# J-Link_On_Board_with_RA4M2.net
KiCad netlist of a schematic drawn in Altium Designer
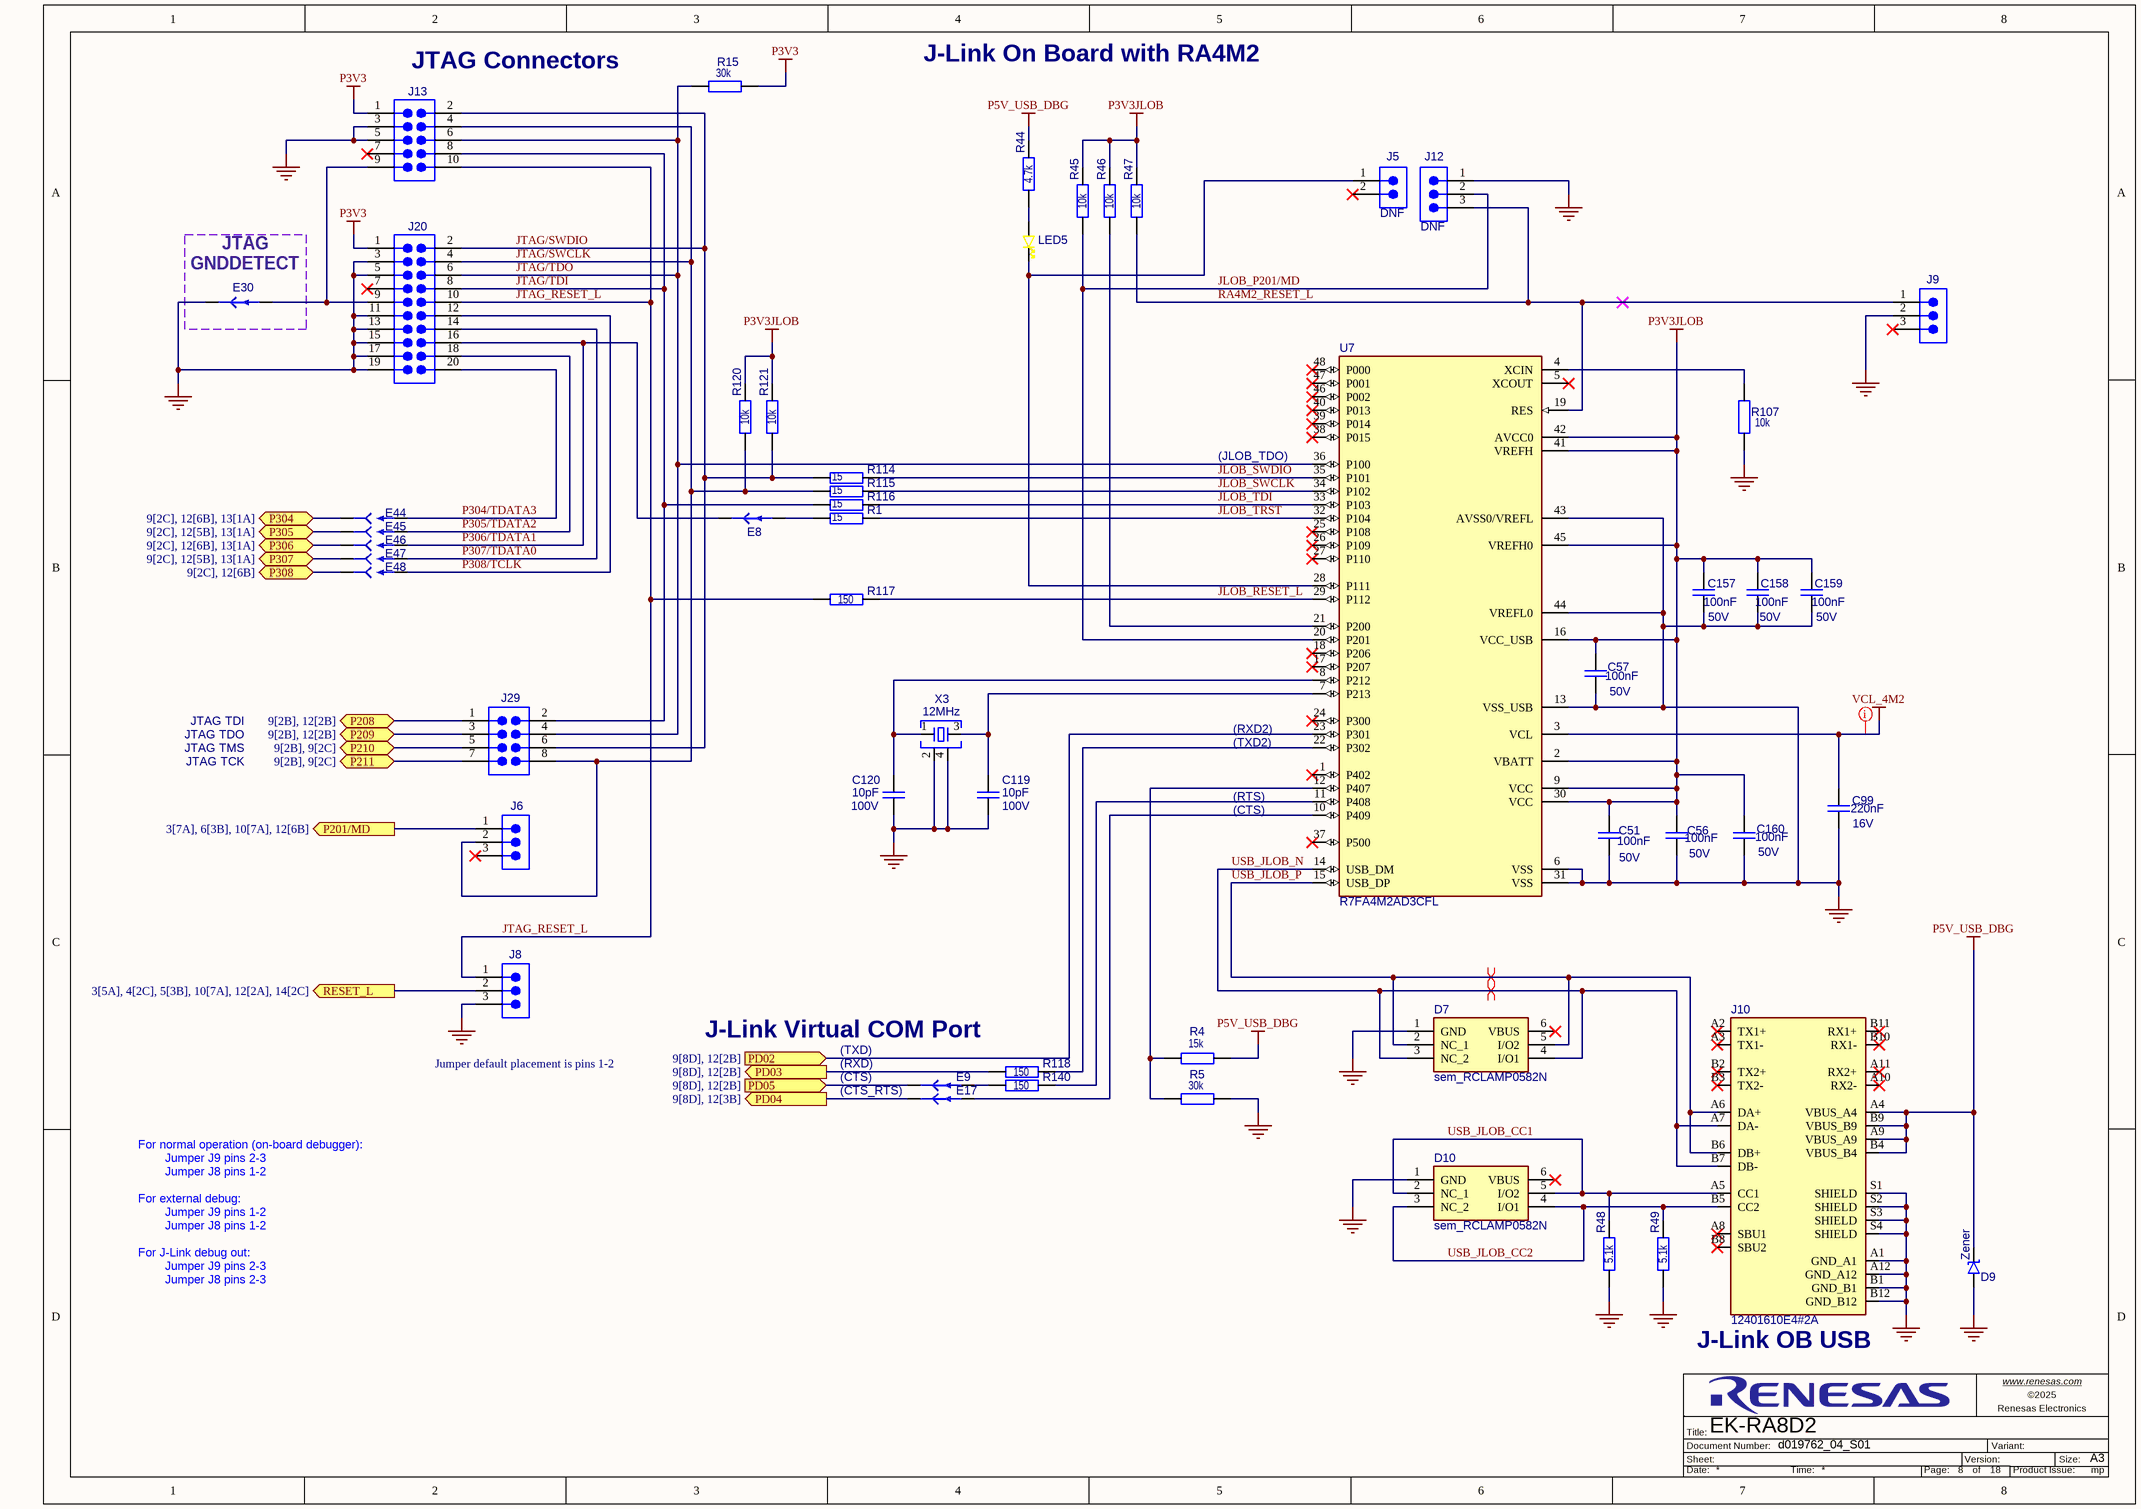
[diagram p0: J-Link On Board with RA4M2.SchDoc]

(export (version "E")
  (design (tool "Eeschema 10.0.6"))
  (components
    (comp (ref "C51")
      (value "100nF")
      (footprint "C_EIA0402_0p55")
      (description "Capacitor,EIA0402,100n,50V,X7R")
      (fields
        (field (name "TOLERANCE") "10%")
        (field (name "OPERATING VOLTAGE MAX") "50V")
        (field (name "Comment") "Capacitor")
      )
      (libsource (lib "ek-ra8d2_mp - Customer") (part "Capacitor"))
    )
    (comp (ref "C56")
      (value "100nF")
      (footprint "C_EIA0402_0p55")
      (description "Capacitor,EIA0402,100n,50V,X7R")
      (fields
        (field (name "TOLERANCE") "10%")
        (field (name "OPERATING VOLTAGE MAX") "50V")
        (field (name "Comment") "Capacitor")
      )
      (libsource (lib "ek-ra8d2_mp - Customer") (part "Capacitor"))
    )
    (comp (ref "C57")
      (value "100nF")
      (footprint "C_EIA0402_0p55")
      (description "Capacitor,EIA0402,100n,50V,X7R")
      (fields
        (field (name "TOLERANCE") "10%")
        (field (name "OPERATING VOLTAGE MAX") "50V")
        (field (name "Comment") "Capacitor")
      )
      (libsource (lib "ek-ra8d2_mp - Customer") (part "Capacitor"))
    )
    (comp (ref "C99")
      (value "220nF")
      (footprint "C_EIA0402_0p55")
      (description "Capacitor,EIA0402,220n,16V,X7R")
      (fields
        (field (name "TOLERANCE") "10%")
        (field (name "OPERATING VOLTAGE MAX") "16V")
        (field (name "Comment") "Capacitor")
      )
      (libsource (lib "ek-ra8d2_mp - Customer") (part "Capacitor"))
    )
    (comp (ref "C119")
      (value "10pF")
      (footprint "C_EIA0402_0p55")
      (description "Capacitor,EIA0402,10p,100V,C0G")
      (fields
        (field (name "TOLERANCE") "5%")
        (field (name "OPERATING VOLTAGE MAX") "100V")
        (field (name "Comment") "Capacitor")
      )
      (libsource (lib "ek-ra8d2_mp - Customer") (part "Capacitor"))
    )
    (comp (ref "C120")
      (value "10pF")
      (footprint "C_EIA0402_0p55")
      (description "Capacitor,EIA0402,10p,100V,C0G")
      (fields
        (field (name "TOLERANCE") "5%")
        (field (name "OPERATING VOLTAGE MAX") "100V")
        (field (name "Comment") "Capacitor")
      )
      (libsource (lib "ek-ra8d2_mp - Customer") (part "Capacitor"))
    )
    (comp (ref "C157")
      (value "100nF")
      (footprint "C_EIA0402_0p55")
      (description "Capacitor,EIA0402,100n,50V,X7R")
      (fields
        (field (name "TOLERANCE") "10%")
        (field (name "OPERATING VOLTAGE MAX") "50V")
        (field (name "Comment") "Capacitor")
      )
      (libsource (lib "ek-ra8d2_mp - Customer") (part "Capacitor"))
    )
    (comp (ref "C158")
      (value "100nF")
      (footprint "C_EIA0402_0p55")
      (description "Capacitor,EIA0402,100n,50V,X7R")
      (fields
        (field (name "TOLERANCE") "10%")
        (field (name "OPERATING VOLTAGE MAX") "50V")
        (field (name "Comment") "Capacitor")
      )
      (libsource (lib "ek-ra8d2_mp - Customer") (part "Capacitor"))
    )
    (comp (ref "C159")
      (value "100nF")
      (footprint "C_EIA0402_0p55")
      (description "Capacitor,EIA0402,100n,50V,X7R")
      (fields
        (field (name "TOLERANCE") "10%")
        (field (name "OPERATING VOLTAGE MAX") "50V")
        (field (name "Comment") "Capacitor")
      )
      (libsource (lib "ek-ra8d2_mp - Customer") (part "Capacitor"))
    )
    (comp (ref "C160")
      (value "100nF")
      (footprint "C_EIA0402_0p55")
      (description "Capacitor,EIA0402,100n,50V,X7R")
      (fields
        (field (name "TOLERANCE") "10%")
        (field (name "OPERATING VOLTAGE MAX") "50V")
        (field (name "Comment") "Capacitor")
      )
      (libsource (lib "ek-ra8d2_mp - Customer") (part "Capacitor"))
    )
    (comp (ref "D7")
      (value "sem_RCLAMP0582N")
      (footprint "sem_SLP-6_SLP1210N6")
      (description "Low Capacitance TVS Diode Array")
      (libsource (lib "ek-ra8d2_mp - Customer") (part "sem_RCLAMP0582N"))
    )
    (comp (ref "D9")
      (value "Zener")
      (footprint "sem_SGP-2_SGP1610N2")
      (description "ESD Suppressor Diode TVS Uni-Dir 22V 55Vc Automotive 2-Pin SGP T/R")
      (libsource (lib "ek-ra8d2_mp - Customer") (part "Zener"))
    )
    (comp (ref "D10")
      (value "sem_RCLAMP0582N")
      (footprint "sem_SLP-6_SLP1210N6")
      (description "Low Capacitance TVS Diode Array")
      (libsource (lib "ek-ra8d2_mp - Customer") (part "sem_RCLAMP0582N"))
    )
    (comp (ref "E8")
      (value "TRACE_CUT_0805")
      (footprint "trace_cut_0805")
      (description "Trace Cut, SMD, 0805 size")
      (libsource (lib "ek-ra8d2_mp - Customer") (part "trace_cut"))
    )
    (comp (ref "E9")
      (value "TRACE_CUT_0805")
      (footprint "trace_cut_0805")
      (description "Trace Cut, SMD, 0805 size")
      (libsource (lib "ek-ra8d2_mp - Customer") (part "trace_cut"))
    )
    (comp (ref "E17")
      (value "TRACE_CUT_0805")
      (footprint "trace_cut_0805")
      (description "Trace Cut, SMD, 0805 size")
      (libsource (lib "ek-ra8d2_mp - Customer") (part "trace_cut"))
    )
    (comp (ref "E30")
      (value "TRACE_CUT_0805")
      (footprint "trace_cut_0805")
      (description "Trace Cut, SMD, 0805 size")
      (libsource (lib "ek-ra8d2_mp - Customer") (part "trace_cut"))
    )
    (comp (ref "E44")
      (value "SOLDER_BRIDGE_0805")
      (footprint "solder_bridge_0805")
      (description "Solder Bridge, SMD, 0805 size")
      (libsource (lib "ek-ra8d2_mp - Customer") (part "solder_bridge"))
    )
    (comp (ref "E45")
      (value "SOLDER_BRIDGE_0805")
      (footprint "solder_bridge_0805")
      (description "Solder Bridge, SMD, 0805 size")
      (libsource (lib "ek-ra8d2_mp - Customer") (part "solder_bridge"))
    )
    (comp (ref "E46")
      (value "SOLDER_BRIDGE_0805")
      (footprint "solder_bridge_0805")
      (description "Solder Bridge, SMD, 0805 size")
      (libsource (lib "ek-ra8d2_mp - Customer") (part "solder_bridge"))
    )
    (comp (ref "E47")
      (value "SOLDER_BRIDGE_0805")
      (footprint "solder_bridge_0805")
      (description "Solder Bridge, SMD, 0805 size")
      (libsource (lib "ek-ra8d2_mp - Customer") (part "solder_bridge"))
    )
    (comp (ref "E48")
      (value "SOLDER_BRIDGE_0805")
      (footprint "solder_bridge_0805")
      (description "Solder Bridge, SMD, 0805 size")
      (libsource (lib "ek-ra8d2_mp - Customer") (part "solder_bridge"))
    )
    (comp (ref "J5")
      (value "NRPN021PAEN-RC")
      (footprint "sul_NRPN021PAEN-RC")
      (description "Header, 2way, 1row, vertical, 2.00mm, THT")
      (fields (field (name "DNF") "DNF"))
      (libsource (lib "ek-ra8d2_mp - Customer") (part "CON_002"))
    )
    (comp (ref "J6")
      (value "2842102-3")
      (footprint "tec_2842102-3")
      (description "Header, 3way, 1row, vertical, 2.00mm, SMD")
      (libsource (lib "ek-ra8d2_mp - Customer") (part "CON_003"))
    )
    (comp (ref "J8")
      (value "2842102-3")
      (footprint "tec_2842102-3")
      (description "Header, 3way, 1row, vertical, 2.00mm, SMD")
      (libsource (lib "ek-ra8d2_mp - Customer") (part "CON_003"))
    )
    (comp (ref "J9")
      (value "2842102-3")
      (footprint "tec_2842102-3")
      (description "Header, 3way, 1row, vertical, 2.00mm, SMD")
      (libsource (lib "ek-ra8d2_mp - Customer") (part "CON_003"))
    )
    (comp (ref "J10")
      (value "12401610E4#2A")
      (footprint "amp_12401610E42A")
      (description "Connector USB 3.2 Gen2 Type C Horizontal SMD")
      (libsource (lib "ek-ra8d2_mp - Customer") (part "USB3.2 Gen2_TypeC"))
    )
    (comp (ref "J12")
      (value "NRPN031PAEN-RC")
      (footprint "sul_NRPN031PAEN-RC")
      (description "Header, 3way, 1row, vertical, 2.00mm, THT")
      (fields (field (name "DNF") "DNF"))
      (libsource (lib "") (part "CON_003_1"))
    )
    (comp (ref "J13")
      (value "FTSH-105-01-F-DV-K-TR")
      (footprint "sam_FTSH-105-01-F-DV-K-TR")
      (description "Header,10way,2row,vertical,1.27mm,SMD")
      (libsource (lib "ek-ra8d2_mp - Customer") (part "CON_010"))
    )
    (comp (ref "J20")
      (value "FTSH-110-01-F-DV-K-TR")
      (footprint "sam_FTSH-110-01-L-DV-K-TR")
      (description "Header,20way,2row,vertical,1.27mm,SMD,gold flash on post")
      (libsource (lib "ek-ra8d2_mp - Customer") (part "CON_020"))
    )
    (comp (ref "J29")
      (value "NRPN042MAMS-RC")
      (footprint "sul_NRPN042MAMS-RC")
      (description "Header, 8way, 2row, vertical, 2.0mm, SMD")
      (libsource (lib "ek-ra8d2_mp - Customer") (part "CON_008"))
    )
    (comp (ref "LED5")
      (value "150060YS75000")
      (footprint "led_0603_y")
      (description "Standard LEDs - SMD Yellow, 590nm 90 to 120 mcd")
      (libsource (lib "ek-ra8d2_mp - Customer") (part "LED_yellow"))
    )
    (comp (ref "R1")
      (value "15")
      (footprint "R_EIA0402")
      (description "Resistor,EIA0402,15,0.0625W")
      (fields (field (name "TOLERANCE") "1%") (field (name "POWER") "62.5mW"))
      (libsource (lib "ek-ra8d2_mp - Customer") (part "Resistor"))
    )
    (comp (ref "R4")
      (value "15k")
      (footprint "R_EIA0402")
      (description "Resistor,EIA0402,15k,0.0625W")
      (fields (field (name "TOLERANCE") "1%") (field (name "POWER") "62.5mW"))
      (libsource (lib "") (part "Resistor_1"))
    )
    (comp (ref "R5")
      (value "30k")
      (footprint "R_EIA0402")
      (description "Resistor,EIA0402,30k,0.0625W")
      (fields (field (name "TOLERANCE") "1%") (field (name "POWER") "62.5mW"))
      (libsource (lib "ek-ra8d2_mp - Customer") (part "Resistor"))
    )
    (comp (ref "R15")
      (value "30k")
      (footprint "R_EIA0402")
      (description "Resistor,EIA0402,30k,0.0625W")
      (fields (field (name "TOLERANCE") "1%") (field (name "POWER") "62.5mW"))
      (libsource (lib "ek-ra8d2_mp - Customer") (part "Resistor"))
    )
    (comp (ref "R44")
      (value "4.7k")
      (footprint "R_EIA0402")
      (description "Resistor,EIA0402,4.7k,0.0625W")
      (fields (field (name "POWER") "62.5mW") (field (name "TOLERANCE") "1%"))
      (libsource (lib "") (part "Resistor_2"))
    )
    (comp (ref "R45")
      (value "10k")
      (footprint "R_EIA0402")
      (description "Resistor,EIA0402,10k,0.0625W")
      (fields (field (name "POWER") "62.5mW") (field (name "TOLERANCE") "1%"))
      (libsource (lib "") (part "Resistor_2"))
    )
    (comp (ref "R46")
      (value "10k")
      (footprint "R_EIA0402")
      (description "Resistor,EIA0402,10k,0.0625W")
      (fields (field (name "POWER") "62.5mW") (field (name "TOLERANCE") "1%"))
      (libsource (lib "") (part "Resistor_2"))
    )
    (comp (ref "R47")
      (value "10k")
      (footprint "R_EIA0402")
      (description "Resistor,EIA0402,10k,0.0625W")
      (fields (field (name "POWER") "62.5mW") (field (name "TOLERANCE") "1%"))
      (libsource (lib "") (part "Resistor_2"))
    )
    (comp (ref "R48")
      (value "5.1k")
      (footprint "R_EIA0402")
      (description "Resistor,EIA0402,5.1k,0.0625W")
      (fields (field (name "POWER") "62.5mW") (field (name "TOLERANCE") "1%"))
      (libsource (lib "") (part "Resistor_2"))
    )
    (comp (ref "R49")
      (value "5.1k")
      (footprint "R_EIA0402")
      (description "Resistor,EIA0402,5.1k,0.0625W")
      (fields (field (name "POWER") "62.5mW") (field (name "TOLERANCE") "1%"))
      (libsource (lib "") (part "Resistor_2"))
    )
    (comp (ref "R107")
      (value "10k")
      (footprint "R_EIA0402")
      (description "Resistor,EIA0402,10k,0.0625W")
      (fields (field (name "POWER") "62.5mW") (field (name "TOLERANCE") "1%"))
      (libsource (lib "") (part "Resistor_2"))
    )
    (comp (ref "R114")
      (value "15")
      (footprint "R_EIA0402")
      (description "Resistor,EIA0402,15,0.0625W")
      (fields (field (name "TOLERANCE") "1%") (field (name "POWER") "62.5mW"))
      (libsource (lib "ek-ra8d2_mp - Customer") (part "Resistor"))
    )
    (comp (ref "R115")
      (value "15")
      (footprint "R_EIA0402")
      (description "Resistor,EIA0402,15,0.0625W")
      (fields (field (name "TOLERANCE") "1%") (field (name "POWER") "62.5mW"))
      (libsource (lib "ek-ra8d2_mp - Customer") (part "Resistor"))
    )
    (comp (ref "R116")
      (value "15")
      (footprint "R_EIA0402")
      (description "Resistor,EIA0402,15,0.0625W")
      (fields (field (name "TOLERANCE") "1%") (field (name "POWER") "62.5mW"))
      (libsource (lib "ek-ra8d2_mp - Customer") (part "Resistor"))
    )
    (comp (ref "R117")
      (value "150")
      (footprint "R_EIA0402")
      (description "Resistor,EIA0402,150,0.0625W")
      (fields (field (name "POWER") "62.5mW") (field (name "TOLERANCE") "1%"))
      (libsource (lib "ek-ra8d2_mp - Customer") (part "Resistor"))
    )
    (comp (ref "R118")
      (value "150")
      (footprint "R_EIA0402")
      (description "Resistor,EIA0402,150,0.0625W")
      (fields (field (name "POWER") "62.5mW") (field (name "TOLERANCE") "1%"))
      (libsource (lib "ek-ra8d2_mp - Customer") (part "Resistor"))
    )
    (comp (ref "R120")
      (value "10k")
      (footprint "R_EIA0402")
      (description "Resistor,EIA0402,10k,0.0625W")
      (fields (field (name "POWER") "62.5mW") (field (name "TOLERANCE") "1%"))
      (libsource (lib "") (part "Resistor_2"))
    )
    (comp (ref "R121")
      (value "10k")
      (footprint "R_EIA0402")
      (description "Resistor,EIA0402,10k,0.0625W")
      (fields (field (name "POWER") "62.5mW") (field (name "TOLERANCE") "1%"))
      (libsource (lib "") (part "Resistor_2"))
    )
    (comp (ref "R140")
      (value "150")
      (footprint "R_EIA0402")
      (description "Resistor,EIA0402,150,0.0625W")
      (fields (field (name "POWER") "62.5mW") (field (name "TOLERANCE") "1%"))
      (libsource (lib "ek-ra8d2_mp - Customer") (part "Resistor"))
    )
    (comp (ref "U7")
      (value "R7FA4M2AD3CFL")
      (footprint "ren_LQFP-48_PLQP0048KB-B")
      (libsource (lib "ek-ra8d2_mp - Customer") (part "ren_R7FA4M2AD3CFL"))
    )
    (comp (ref "X3")
      (value "12MHz")
      (footprint "ecs_ECX-2236B")
      (description "Crystal, 12.000MHz, 10 pF, 2.5x2")
      (fields (field (name "TOLERANCE") "10ppm") (field (name "Comment") "ECS-120-10-36B-CWY-TR"))
      (libsource (lib "ek-ra8d2_mp - Customer") (part "Crystal_4pin"))
    )
  )
  (nets
    (net (code "1") (name "/JLOB_P201{slash}MD") (class "Default")
      (node (ref "J12") (pin "2") (pinfunction "2_2") (pintype "passive"))
      (node (ref "R45") (pin "1") (pinfunction "1_1") (pintype "passive"))
      (node (ref "U7") (pin "20") (pinfunction "P201_20") (pintype "bidirectional"))
    )
    (net (code "2") (name "/JLOB_RESET_L") (class "Default")
      (node (ref "R117") (pin "2") (pinfunction "2_2") (pintype "passive"))
      (node (ref "U7") (pin "29") (pinfunction "P112_29") (pintype "bidirectional"))
    )
    (net (code "3") (name "/JLOB_SWCLK") (class "Default")
      (node (ref "R115") (pin "2") (pinfunction "2_2") (pintype "passive"))
      (node (ref "U7") (pin "34") (pinfunction "P102_34") (pintype "bidirectional"))
    )
    (net (code "4") (name "/JLOB_SWDIO") (class "Default")
      (node (ref "R114") (pin "2") (pinfunction "2_2") (pintype "passive"))
      (node (ref "U7") (pin "35") (pinfunction "P101_35") (pintype "bidirectional"))
    )
    (net (code "5") (name "/JLOB_TDI") (class "Default")
      (node (ref "R116") (pin "2") (pinfunction "2_2") (pintype "passive"))
      (node (ref "U7") (pin "33") (pinfunction "P103_33") (pintype "bidirectional"))
    )
    (net (code "6") (name "/JLOB_TRST") (class "Default")
      (node (ref "R1") (pin "2") (pinfunction "2_2") (pintype "passive"))
      (node (ref "U7") (pin "32") (pinfunction "P104_32") (pintype "bidirectional"))
    )
    (net (code "7") (name "/JTAG_RESET_L") (class "Default")
      (node (ref "J13") (pin "10") (pinfunction "10_10") (pintype "passive"))
      (node (ref "J20") (pin "10") (pinfunction "10_10") (pintype "passive"))
      (node (ref "J8") (pin "1") (pinfunction "1_1") (pintype "passive"))
      (node (ref "R117") (pin "1") (pinfunction "1_1") (pintype "passive"))
    )
    (net (code "8") (name "/JTAG{slash}SWCLK") (class "Default")
      (node (ref "J13") (pin "4") (pinfunction "4_4") (pintype "passive"))
      (node (ref "J20") (pin "4") (pinfunction "4_4") (pintype "passive"))
      (node (ref "J29") (pin "8") (pinfunction "8_8") (pintype "passive"))
      (node (ref "J6") (pin "2") (pinfunction "2_2") (pintype "passive"))
      (node (ref "R115") (pin "1") (pinfunction "1_1") (pintype "passive"))
      (node (ref "R120") (pin "1") (pinfunction "1_1") (pintype "passive"))
    )
    (net (code "9") (name "/JTAG{slash}SWDIO") (class "Default")
      (node (ref "J13") (pin "2") (pinfunction "2_2") (pintype "passive"))
      (node (ref "J20") (pin "2") (pinfunction "2_2") (pintype "passive"))
      (node (ref "J29") (pin "6") (pinfunction "6_6") (pintype "passive"))
      (node (ref "R114") (pin "1") (pinfunction "1_1") (pintype "passive"))
      (node (ref "R121") (pin "1") (pinfunction "1_1") (pintype "passive"))
    )
    (net (code "10") (name "/JTAG{slash}TDI") (class "Default")
      (node (ref "J13") (pin "8") (pinfunction "8_8") (pintype "passive"))
      (node (ref "J20") (pin "8") (pinfunction "8_8") (pintype "passive"))
      (node (ref "J29") (pin "2") (pinfunction "2_2") (pintype "passive"))
      (node (ref "R116") (pin "1") (pinfunction "1_1") (pintype "passive"))
    )
    (net (code "11") (name "/JTAG{slash}TDO") (class "Default")
      (node (ref "J13") (pin "6") (pinfunction "6_6") (pintype "passive"))
      (node (ref "J20") (pin "6") (pinfunction "6_6") (pintype "passive"))
      (node (ref "J29") (pin "4") (pinfunction "4_4") (pintype "passive"))
      (node (ref "R15") (pin "1") (pinfunction "1_1") (pintype "passive"))
      (node (ref "U7") (pin "36") (pinfunction "P100_36") (pintype "bidirectional"))
    )
    (net (code "12") (name "/P201{slash}MD") (class "Default")
      (node (ref "J6") (pin "1") (pinfunction "1_1") (pintype "passive"))
    )
    (net (code "13") (name "/P208") (class "Default")
      (node (ref "J29") (pin "1") (pinfunction "1_1") (pintype "passive"))
    )
    (net (code "14") (name "/P209") (class "Default")
      (node (ref "J29") (pin "3") (pinfunction "3_3") (pintype "passive"))
    )
    (net (code "15") (name "/P210") (class "Default")
      (node (ref "J29") (pin "5") (pinfunction "5_5") (pintype "passive"))
    )
    (net (code "16") (name "/P211") (class "Default")
      (node (ref "J29") (pin "7") (pinfunction "7_7") (pintype "passive"))
    )
    (net (code "17") (name "/P304") (class "Default")
      (node (ref "E44") (pin "1") (pinfunction "1_1") (pintype "passive"))
    )
    (net (code "18") (name "/P304{slash}TDATA3") (class "Default")
      (node (ref "E44") (pin "2") (pinfunction "2_2") (pintype "passive"))
      (node (ref "J20") (pin "20") (pinfunction "20_20") (pintype "passive"))
    )
    (net (code "19") (name "/P305") (class "Default")
      (node (ref "E45") (pin "1") (pinfunction "1_1") (pintype "passive"))
    )
    (net (code "20") (name "/P305{slash}TDATA2") (class "Default")
      (node (ref "E45") (pin "2") (pinfunction "2_2") (pintype "passive"))
      (node (ref "J20") (pin "18") (pinfunction "18_18") (pintype "passive"))
    )
    (net (code "21") (name "/P306") (class "Default")
      (node (ref "E46") (pin "1") (pinfunction "1_1") (pintype "passive"))
    )
    (net (code "22") (name "/P306{slash}TDATA1") (class "Default")
      (node (ref "E46") (pin "2") (pinfunction "2_2") (pintype "passive"))
      (node (ref "E8") (pin "1") (pinfunction "1_1") (pintype "passive"))
      (node (ref "J20") (pin "16") (pinfunction "16_16") (pintype "passive"))
    )
    (net (code "23") (name "/P307") (class "Default")
      (node (ref "E47") (pin "1") (pinfunction "1_1") (pintype "passive"))
    )
    (net (code "24") (name "/P307{slash}TDATA0") (class "Default")
      (node (ref "E47") (pin "2") (pinfunction "2_2") (pintype "passive"))
      (node (ref "J20") (pin "14") (pinfunction "14_14") (pintype "passive"))
    )
    (net (code "25") (name "/P308") (class "Default")
      (node (ref "E48") (pin "1") (pinfunction "1_1") (pintype "passive"))
    )
    (net (code "26") (name "/P308{slash}TCLK") (class "Default")
      (node (ref "E48") (pin "2") (pinfunction "2_2") (pintype "passive"))
      (node (ref "J20") (pin "12") (pinfunction "12_12") (pintype "passive"))
    )
    (net (code "27") (name "/PD02") (class "Default")
      (node (ref "U7") (pin "23") (pinfunction "P301_23") (pintype "bidirectional"))
    )
    (net (code "28") (name "/PD03") (class "Default")
      (node (ref "R118") (pin "1") (pinfunction "1_1") (pintype "passive"))
    )
    (net (code "29") (name "/PD04") (class "Default")
      (node (ref "E17") (pin "1") (pinfunction "1_1") (pintype "passive"))
    )
    (net (code "30") (name "/PD05") (class "Default")
      (node (ref "E9") (pin "1") (pinfunction "1_1") (pintype "passive"))
    )
    (net (code "31") (name "/RA4M2_RESET_L") (class "Default")
      (node (ref "J12") (pin "3") (pinfunction "3_3") (pintype "passive"))
      (node (ref "J9") (pin "1") (pinfunction "1_1") (pintype "passive"))
      (node (ref "R47") (pin "1") (pinfunction "1_1") (pintype "passive"))
      (node (ref "U7") (pin "19") (pinfunction "RES_19") (pintype "input"))
    )
    (net (code "32") (name "/RESET_L") (class "Default")
      (node (ref "J8") (pin "2") (pinfunction "2_2") (pintype "passive"))
    )
    (net (code "33") (name "/USB_JLOB_CC1") (class "Default")
      (node (ref "D10") (pin "2") (pinfunction "NC_1_2") (pintype "passive"))
      (node (ref "D10") (pin "5") (pinfunction "I/O2_5") (pintype "passive"))
      (node (ref "J10") (pin "A5") (pinfunction "CC1_A5") (pintype "passive"))
      (node (ref "R48") (pin "2") (pinfunction "2_2") (pintype "passive"))
    )
    (net (code "34") (name "/USB_JLOB_CC2") (class "Default")
      (node (ref "D10") (pin "3") (pinfunction "NC_2_3") (pintype "passive"))
      (node (ref "D10") (pin "4") (pinfunction "I/O1_4") (pintype "passive"))
      (node (ref "J10") (pin "B5") (pinfunction "CC2_B5") (pintype "passive"))
      (node (ref "R49") (pin "2") (pinfunction "2_2") (pintype "passive"))
    )
    (net (code "35") (name "/USB_JLOB_N") (class "Default")
      (node (ref "D7") (pin "3") (pinfunction "NC_2_3") (pintype "passive"))
      (node (ref "D7") (pin "4") (pinfunction "I/O1_4") (pintype "passive"))
      (node (ref "J10") (pin "A7") (pinfunction "DA-_A7") (pintype "passive"))
      (node (ref "J10") (pin "B7") (pinfunction "DB-_B7") (pintype "passive"))
      (node (ref "U7") (pin "14") (pinfunction "USB_DM_14") (pintype "bidirectional"))
    )
    (net (code "36") (name "/USB_JLOB_P") (class "Default")
      (node (ref "D7") (pin "2") (pinfunction "NC_1_2") (pintype "passive"))
      (node (ref "D7") (pin "5") (pinfunction "I/O2_5") (pintype "passive"))
      (node (ref "J10") (pin "A6") (pinfunction "DA+_A6") (pintype "passive"))
      (node (ref "J10") (pin "B6") (pinfunction "DB+_B6") (pintype "passive"))
      (node (ref "U7") (pin "15") (pinfunction "USB_DP_15") (pintype "bidirectional"))
    )
    (net (code "37") (name "GND") (class "Default")
      (node (ref "C119") (pin "2") (pinfunction "2_2") (pintype "passive"))
      (node (ref "C120") (pin "2") (pinfunction "2_2") (pintype "passive"))
      (node (ref "C157") (pin "1") (pinfunction "1_1") (pintype "passive"))
      (node (ref "C158") (pin "1") (pinfunction "1_1") (pintype "passive"))
      (node (ref "C159") (pin "1") (pinfunction "1_1") (pintype "passive"))
      (node (ref "C160") (pin "1") (pinfunction "1_1") (pintype "passive"))
      (node (ref "C51") (pin "1") (pinfunction "1_1") (pintype "passive"))
      (node (ref "C56") (pin "1") (pinfunction "1_1") (pintype "passive"))
      (node (ref "C57") (pin "1") (pinfunction "1_1") (pintype "passive"))
      (node (ref "C99") (pin "1") (pinfunction "1_1") (pintype "passive"))
      (node (ref "D10") (pin "1") (pinfunction "GND_1") (pintype "passive"))
      (node (ref "D7") (pin "1") (pinfunction "GND_1") (pintype "passive"))
      (node (ref "D9") (pin "2") (pinfunction "A_2") (pintype "passive"))
      (node (ref "E30") (pin "1") (pinfunction "1_1") (pintype "passive"))
      (node (ref "J10") (pin "A1") (pinfunction "GND_A1_A1") (pintype "passive"))
      (node (ref "J10") (pin "A12") (pinfunction "GND_A12_A12") (pintype "passive"))
      (node (ref "J10") (pin "B1") (pinfunction "GND_B1_B1") (pintype "passive"))
      (node (ref "J10") (pin "B12") (pinfunction "GND_B12_B12") (pintype "passive"))
      (node (ref "J10") (pin "S1") (pinfunction "SHIELD_S1") (pintype "passive"))
      (node (ref "J10") (pin "S2") (pinfunction "SHIELD_S2") (pintype "passive"))
      (node (ref "J10") (pin "S3") (pinfunction "SHIELD_S3") (pintype "passive"))
      (node (ref "J10") (pin "S4") (pinfunction "SHIELD_S4") (pintype "passive"))
      (node (ref "J12") (pin "1") (pinfunction "1_1") (pintype "passive"))
      (node (ref "J13") (pin "3") (pinfunction "3_3") (pintype "passive"))
      (node (ref "J13") (pin "5") (pinfunction "5_5") (pintype "passive"))
      (node (ref "J20") (pin "11") (pinfunction "11_11") (pintype "passive"))
      (node (ref "J20") (pin "13") (pinfunction "13_13") (pintype "passive"))
      (node (ref "J20") (pin "15") (pinfunction "15_15") (pintype "passive"))
      (node (ref "J20") (pin "17") (pinfunction "17_17") (pintype "passive"))
      (node (ref "J20") (pin "19") (pinfunction "19_19") (pintype "passive"))
      (node (ref "J20") (pin "3") (pinfunction "3_3") (pintype "passive"))
      (node (ref "J20") (pin "5") (pinfunction "5_5") (pintype "passive"))
      (node (ref "J8") (pin "3") (pinfunction "3_3") (pintype "passive"))
      (node (ref "J9") (pin "2") (pinfunction "2_2") (pintype "passive"))
      (node (ref "R107") (pin "1") (pinfunction "1_1") (pintype "passive"))
      (node (ref "R48") (pin "1") (pinfunction "1_1") (pintype "passive"))
      (node (ref "R49") (pin "1") (pinfunction "1_1") (pintype "passive"))
      (node (ref "R5") (pin "2") (pinfunction "2_2") (pintype "passive"))
      (node (ref "U7") (pin "13") (pinfunction "VSS_USB_13") (pintype "power_in"))
      (node (ref "U7") (pin "31") (pinfunction "VSS_31") (pintype "power_in"))
      (node (ref "U7") (pin "43") (pinfunction "AVSS0/VREFL_43") (pintype "power_in"))
      (node (ref "U7") (pin "44") (pinfunction "VREFL0_44") (pintype "power_in"))
      (node (ref "U7") (pin "6") (pinfunction "VSS_6") (pintype "power_in"))
      (node (ref "X3") (pin "2") (pinfunction "2_2") (pintype "passive"))
      (node (ref "X3") (pin "4") (pinfunction "4_4") (pintype "passive"))
    )
    (net (code "38") (name "Net-(E8-Pad2)") (class "Default")
      (node (ref "E8") (pin "2") (pinfunction "2_2") (pintype "passive"))
      (node (ref "R1") (pin "1") (pinfunction "1_1") (pintype "passive"))
    )
    (net (code "39") (name "Net-(E9-Pad2)") (class "Default")
      (node (ref "E9") (pin "2") (pinfunction "2_2") (pintype "passive"))
      (node (ref "R140") (pin "1") (pinfunction "1_1") (pintype "passive"))
    )
    (net (code "40") (name "Net-(E30-Pad2)") (class "Default")
      (node (ref "E30") (pin "2") (pinfunction "2_2") (pintype "passive"))
      (node (ref "J13") (pin "9") (pinfunction "9_9") (pintype "passive"))
      (node (ref "J20") (pin "9") (pinfunction "9_9") (pintype "passive"))
    )
    (net (code "41") (name "Net-(LED5-A)") (class "Default")
      (node (ref "LED5") (pin "2") (pinfunction "A_2") (pintype "passive"))
      (node (ref "R44") (pin "1") (pinfunction "1_1") (pintype "passive"))
    )
    (net (code "42") (name "Net-(LED5-K)") (class "Default")
      (node (ref "J5") (pin "1") (pinfunction "1_1") (pintype "passive"))
      (node (ref "LED5") (pin "1") (pinfunction "K_1") (pintype "passive"))
      (node (ref "U7") (pin "28") (pinfunction "P111_28") (pintype "bidirectional"))
    )
    (net (code "43") (name "Net-(U7-P200)") (class "Default")
      (node (ref "R46") (pin "1") (pinfunction "1_1") (pintype "passive"))
      (node (ref "U7") (pin "21") (pinfunction "P200_21") (pintype "bidirectional"))
    )
    (net (code "44") (name "Net-(U7-P212)") (class "Default")
      (node (ref "C120") (pin "1") (pinfunction "1_1") (pintype "passive"))
      (node (ref "U7") (pin "8") (pinfunction "P212_8") (pintype "bidirectional"))
      (node (ref "X3") (pin "1") (pinfunction "1_1") (pintype "passive"))
    )
    (net (code "45") (name "Net-(U7-P213)") (class "Default")
      (node (ref "C119") (pin "1") (pinfunction "1_1") (pintype "passive"))
      (node (ref "U7") (pin "7") (pinfunction "P213_7") (pintype "bidirectional"))
      (node (ref "X3") (pin "3") (pinfunction "3_3") (pintype "passive"))
    )
    (net (code "46") (name "Net-(U7-P302)") (class "Default")
      (node (ref "R118") (pin "2") (pinfunction "2_2") (pintype "passive"))
      (node (ref "U7") (pin "22") (pinfunction "P302_22") (pintype "bidirectional"))
    )
    (net (code "47") (name "Net-(U7-P407)") (class "Default")
      (node (ref "R4") (pin "2") (pinfunction "2_2") (pintype "passive"))
      (node (ref "R5") (pin "1") (pinfunction "1_1") (pintype "passive"))
      (node (ref "U7") (pin "12") (pinfunction "P407_12") (pintype "bidirectional"))
    )
    (net (code "48") (name "Net-(U7-P408)") (class "Default")
      (node (ref "R140") (pin "2") (pinfunction "2_2") (pintype "passive"))
      (node (ref "U7") (pin "11") (pinfunction "P408_11") (pintype "bidirectional"))
    )
    (net (code "49") (name "Net-(U7-P409)") (class "Default")
      (node (ref "E17") (pin "2") (pinfunction "2_2") (pintype "passive"))
      (node (ref "U7") (pin "10") (pinfunction "P409_10") (pintype "bidirectional"))
    )
    (net (code "50") (name "Net-(U7-XCIN)") (class "Default")
      (node (ref "R107") (pin "2") (pinfunction "2_2") (pintype "passive"))
      (node (ref "U7") (pin "4") (pinfunction "XCIN_4") (pintype "passive"))
    )
    (net (code "51") (name "P3V3") (class "Default")
      (node (ref "J13") (pin "1") (pinfunction "1_1") (pintype "passive"))
      (node (ref "J20") (pin "1") (pinfunction "1_1") (pintype "passive"))
      (node (ref "R15") (pin "2") (pinfunction "2_2") (pintype "passive"))
    )
    (net (code "52") (name "P3V3JLOB") (class "Default")
      (node (ref "C157") (pin "2") (pinfunction "2_2") (pintype "passive"))
      (node (ref "C158") (pin "2") (pinfunction "2_2") (pintype "passive"))
      (node (ref "C159") (pin "2") (pinfunction "2_2") (pintype "passive"))
      (node (ref "C160") (pin "2") (pinfunction "2_2") (pintype "passive"))
      (node (ref "C51") (pin "2") (pinfunction "2_2") (pintype "passive"))
      (node (ref "C56") (pin "2") (pinfunction "2_2") (pintype "passive"))
      (node (ref "C57") (pin "2") (pinfunction "2_2") (pintype "passive"))
      (node (ref "R120") (pin "2") (pinfunction "2_2") (pintype "passive"))
      (node (ref "R121") (pin "2") (pinfunction "2_2") (pintype "passive"))
      (node (ref "R45") (pin "2") (pinfunction "2_2") (pintype "passive"))
      (node (ref "R46") (pin "2") (pinfunction "2_2") (pintype "passive"))
      (node (ref "R47") (pin "2") (pinfunction "2_2") (pintype "passive"))
      (node (ref "U7") (pin "16") (pinfunction "VCC_USB_16") (pintype "power_in"))
      (node (ref "U7") (pin "2") (pinfunction "VBATT_2") (pintype "power_in"))
      (node (ref "U7") (pin "30") (pinfunction "VCC_30") (pintype "power_in"))
      (node (ref "U7") (pin "41") (pinfunction "VREFH_41") (pintype "power_in"))
      (node (ref "U7") (pin "42") (pinfunction "AVCC0_42") (pintype "power_in"))
      (node (ref "U7") (pin "45") (pinfunction "VREFH0_45") (pintype "power_in"))
      (node (ref "U7") (pin "9") (pinfunction "VCC_9") (pintype "power_in"))
    )
    (net (code "53") (name "P5V_USB_DBG") (class "Default")
      (node (ref "D9") (pin "1") (pinfunction "K_1") (pintype "passive"))
      (node (ref "J10") (pin "A4") (pinfunction "VBUS_A4_A4") (pintype "passive"))
      (node (ref "J10") (pin "A9") (pinfunction "VBUS_A9_A9") (pintype "passive"))
      (node (ref "J10") (pin "B4") (pinfunction "VBUS_B4_B4") (pintype "passive"))
      (node (ref "J10") (pin "B9") (pinfunction "VBUS_B9_B9") (pintype "passive"))
      (node (ref "R4") (pin "1") (pinfunction "1_1") (pintype "passive"))
      (node (ref "R44") (pin "2") (pinfunction "2_2") (pintype "passive"))
    )
    (net (code "54") (name "VCL_4M2") (class "Default")
      (node (ref "C99") (pin "2") (pinfunction "2_2") (pintype "passive"))
      (node (ref "U7") (pin "3") (pinfunction "VCL_3") (pintype "power_in"))
    )
    (net (code "55") (name "unconnected-(D7-VBUS-Pad6)") (class "Default")
      (node (ref "D7") (pin "6") (pinfunction "VBUS_6") (pintype "passive+no_connect"))
    )
    (net (code "56") (name "unconnected-(D10-VBUS-Pad6)") (class "Default")
      (node (ref "D10") (pin "6") (pinfunction "VBUS_6") (pintype "passive+no_connect"))
    )
    (net (code "57") (name "unconnected-(J5-Pad2)") (class "Default")
      (node (ref "J5") (pin "2") (pinfunction "2_2") (pintype "passive+no_connect"))
    )
    (net (code "58") (name "unconnected-(J6-Pad3)") (class "Default")
      (node (ref "J6") (pin "3") (pinfunction "3_3") (pintype "passive+no_connect"))
    )
    (net (code "59") (name "unconnected-(J9-Pad3)") (class "Default")
      (node (ref "J9") (pin "3") (pinfunction "3_3") (pintype "passive+no_connect"))
    )
    (net (code "60") (name "unconnected-(J10-RX1+-PadB11)") (class "Default")
      (node (ref "J10") (pin "B11") (pinfunction "RX1+_B11") (pintype "passive+no_connect"))
    )
    (net (code "61") (name "unconnected-(J10-RX1--PadB10)") (class "Default")
      (node (ref "J10") (pin "B10") (pinfunction "RX1-_B10") (pintype "passive+no_connect"))
    )
    (net (code "62") (name "unconnected-(J10-RX2+-PadA11)") (class "Default")
      (node (ref "J10") (pin "A11") (pinfunction "RX2+_A11") (pintype "passive+no_connect"))
    )
    (net (code "63") (name "unconnected-(J10-RX2--PadA10)") (class "Default")
      (node (ref "J10") (pin "A10") (pinfunction "RX2-_A10") (pintype "passive+no_connect"))
    )
    (net (code "64") (name "unconnected-(J10-SBU1-PadA8)") (class "Default")
      (node (ref "J10") (pin "A8") (pinfunction "SBU1_A8") (pintype "passive+no_connect"))
    )
    (net (code "65") (name "unconnected-(J10-SBU2-PadB8)") (class "Default")
      (node (ref "J10") (pin "B8") (pinfunction "SBU2_B8") (pintype "passive+no_connect"))
    )
    (net (code "66") (name "unconnected-(J10-TX1+-PadA2)") (class "Default")
      (node (ref "J10") (pin "A2") (pinfunction "TX1+_A2") (pintype "passive+no_connect"))
    )
    (net (code "67") (name "unconnected-(J10-TX1--PadA3)") (class "Default")
      (node (ref "J10") (pin "A3") (pinfunction "TX1-_A3") (pintype "passive+no_connect"))
    )
    (net (code "68") (name "unconnected-(J10-TX2+-PadB2)") (class "Default")
      (node (ref "J10") (pin "B2") (pinfunction "TX2+_B2") (pintype "passive+no_connect"))
    )
    (net (code "69") (name "unconnected-(J10-TX2--PadB3)") (class "Default")
      (node (ref "J10") (pin "B3") (pinfunction "TX2-_B3") (pintype "passive+no_connect"))
    )
    (net (code "70") (name "unconnected-(J13-Pad7)") (class "Default")
      (node (ref "J13") (pin "7") (pinfunction "7_7") (pintype "passive+no_connect"))
    )
    (net (code "71") (name "unconnected-(J20-Pad7)") (class "Default")
      (node (ref "J20") (pin "7") (pinfunction "7_7") (pintype "passive+no_connect"))
    )
    (net (code "72") (name "unconnected-(U7-P000-Pad48)") (class "Default")
      (node (ref "U7") (pin "48") (pinfunction "P000_48") (pintype "bidirectional+no_connect"))
    )
    (net (code "73") (name "unconnected-(U7-P001-Pad47)") (class "Default")
      (node (ref "U7") (pin "47") (pinfunction "P001_47") (pintype "bidirectional+no_connect"))
    )
    (net (code "74") (name "unconnected-(U7-P002-Pad46)") (class "Default")
      (node (ref "U7") (pin "46") (pinfunction "P002_46") (pintype "bidirectional+no_connect"))
    )
    (net (code "75") (name "unconnected-(U7-P013-Pad40)") (class "Default")
      (node (ref "U7") (pin "40") (pinfunction "P013_40") (pintype "bidirectional+no_connect"))
    )
    (net (code "76") (name "unconnected-(U7-P014-Pad39)") (class "Default")
      (node (ref "U7") (pin "39") (pinfunction "P014_39") (pintype "bidirectional+no_connect"))
    )
    (net (code "77") (name "unconnected-(U7-P015-Pad38)") (class "Default")
      (node (ref "U7") (pin "38") (pinfunction "P015_38") (pintype "bidirectional+no_connect"))
    )
    (net (code "78") (name "unconnected-(U7-P108-Pad25)") (class "Default")
      (node (ref "U7") (pin "25") (pinfunction "P108_25") (pintype "bidirectional+no_connect"))
    )
    (net (code "79") (name "unconnected-(U7-P109-Pad26)") (class "Default")
      (node (ref "U7") (pin "26") (pinfunction "P109_26") (pintype "bidirectional+no_connect"))
    )
    (net (code "80") (name "unconnected-(U7-P110-Pad27)") (class "Default")
      (node (ref "U7") (pin "27") (pinfunction "P110_27") (pintype "bidirectional+no_connect"))
    )
    (net (code "81") (name "unconnected-(U7-P206-Pad18)") (class "Default")
      (node (ref "U7") (pin "18") (pinfunction "P206_18") (pintype "bidirectional+no_connect"))
    )
    (net (code "82") (name "unconnected-(U7-P207-Pad17)") (class "Default")
      (node (ref "U7") (pin "17") (pinfunction "P207_17") (pintype "bidirectional+no_connect"))
    )
    (net (code "83") (name "unconnected-(U7-P300-Pad24)") (class "Default")
      (node (ref "U7") (pin "24") (pinfunction "P300_24") (pintype "bidirectional+no_connect"))
    )
    (net (code "84") (name "unconnected-(U7-P402-Pad1)") (class "Default")
      (node (ref "U7") (pin "1") (pinfunction "P402_1") (pintype "bidirectional+no_connect"))
    )
    (net (code "85") (name "unconnected-(U7-P500-Pad37)") (class "Default")
      (node (ref "U7") (pin "37") (pinfunction "P500_37") (pintype "bidirectional+no_connect"))
    )
    (net (code "86") (name "unconnected-(U7-XCOUT-Pad5)") (class "Default")
      (node (ref "U7") (pin "5") (pinfunction "XCOUT_5") (pintype "passive+no_connect"))
    )
  )
)
